# main.net
KiCad netlist of a schematic drawn in EAGLE
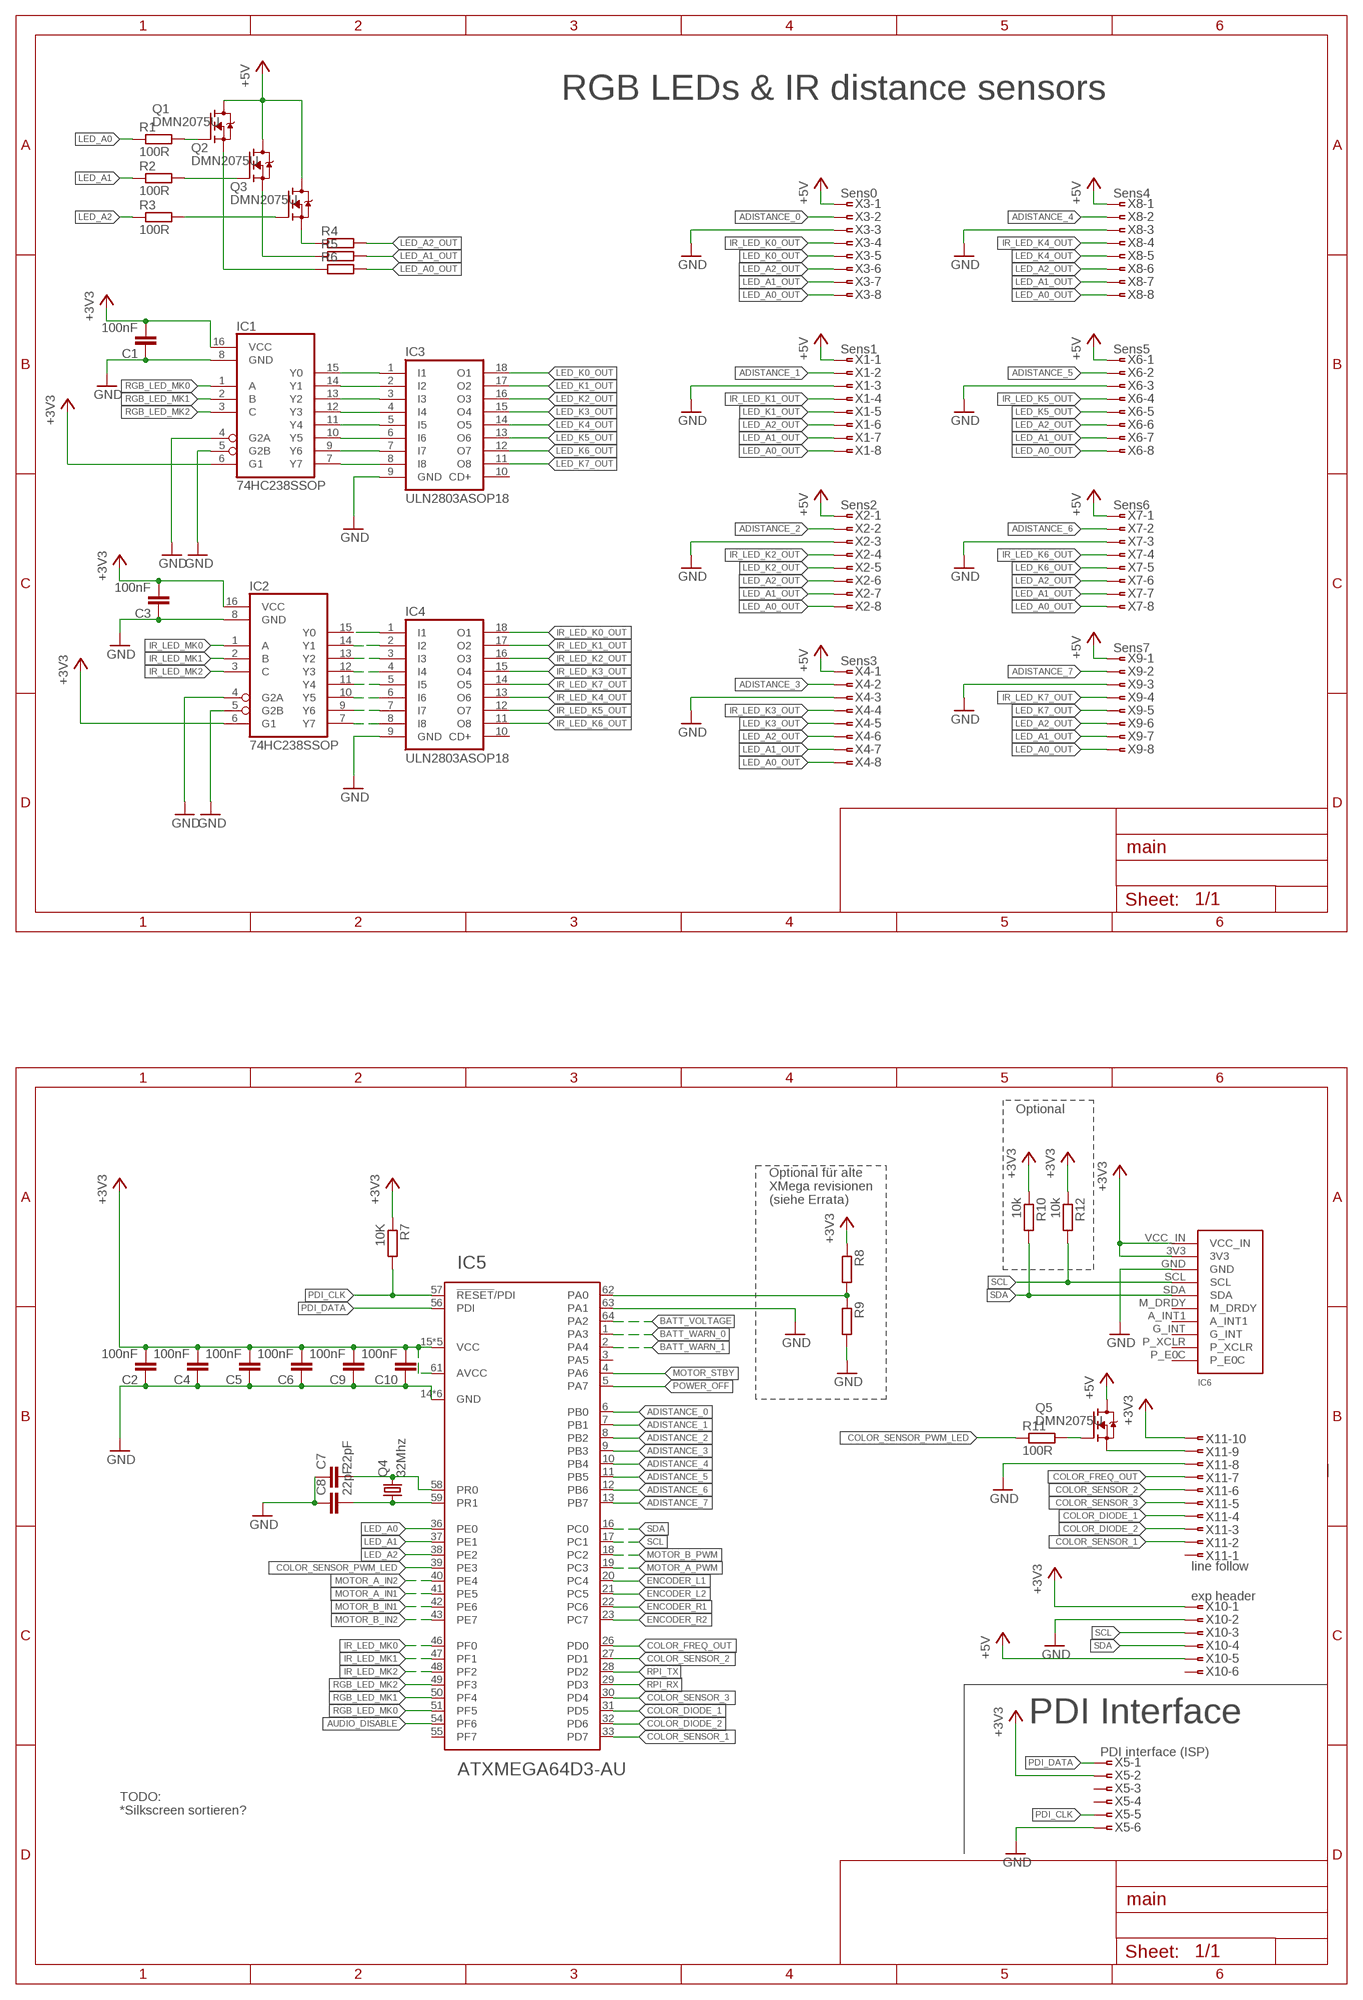
[diagram p0: schematic, sheet 1, part 1 of 2]
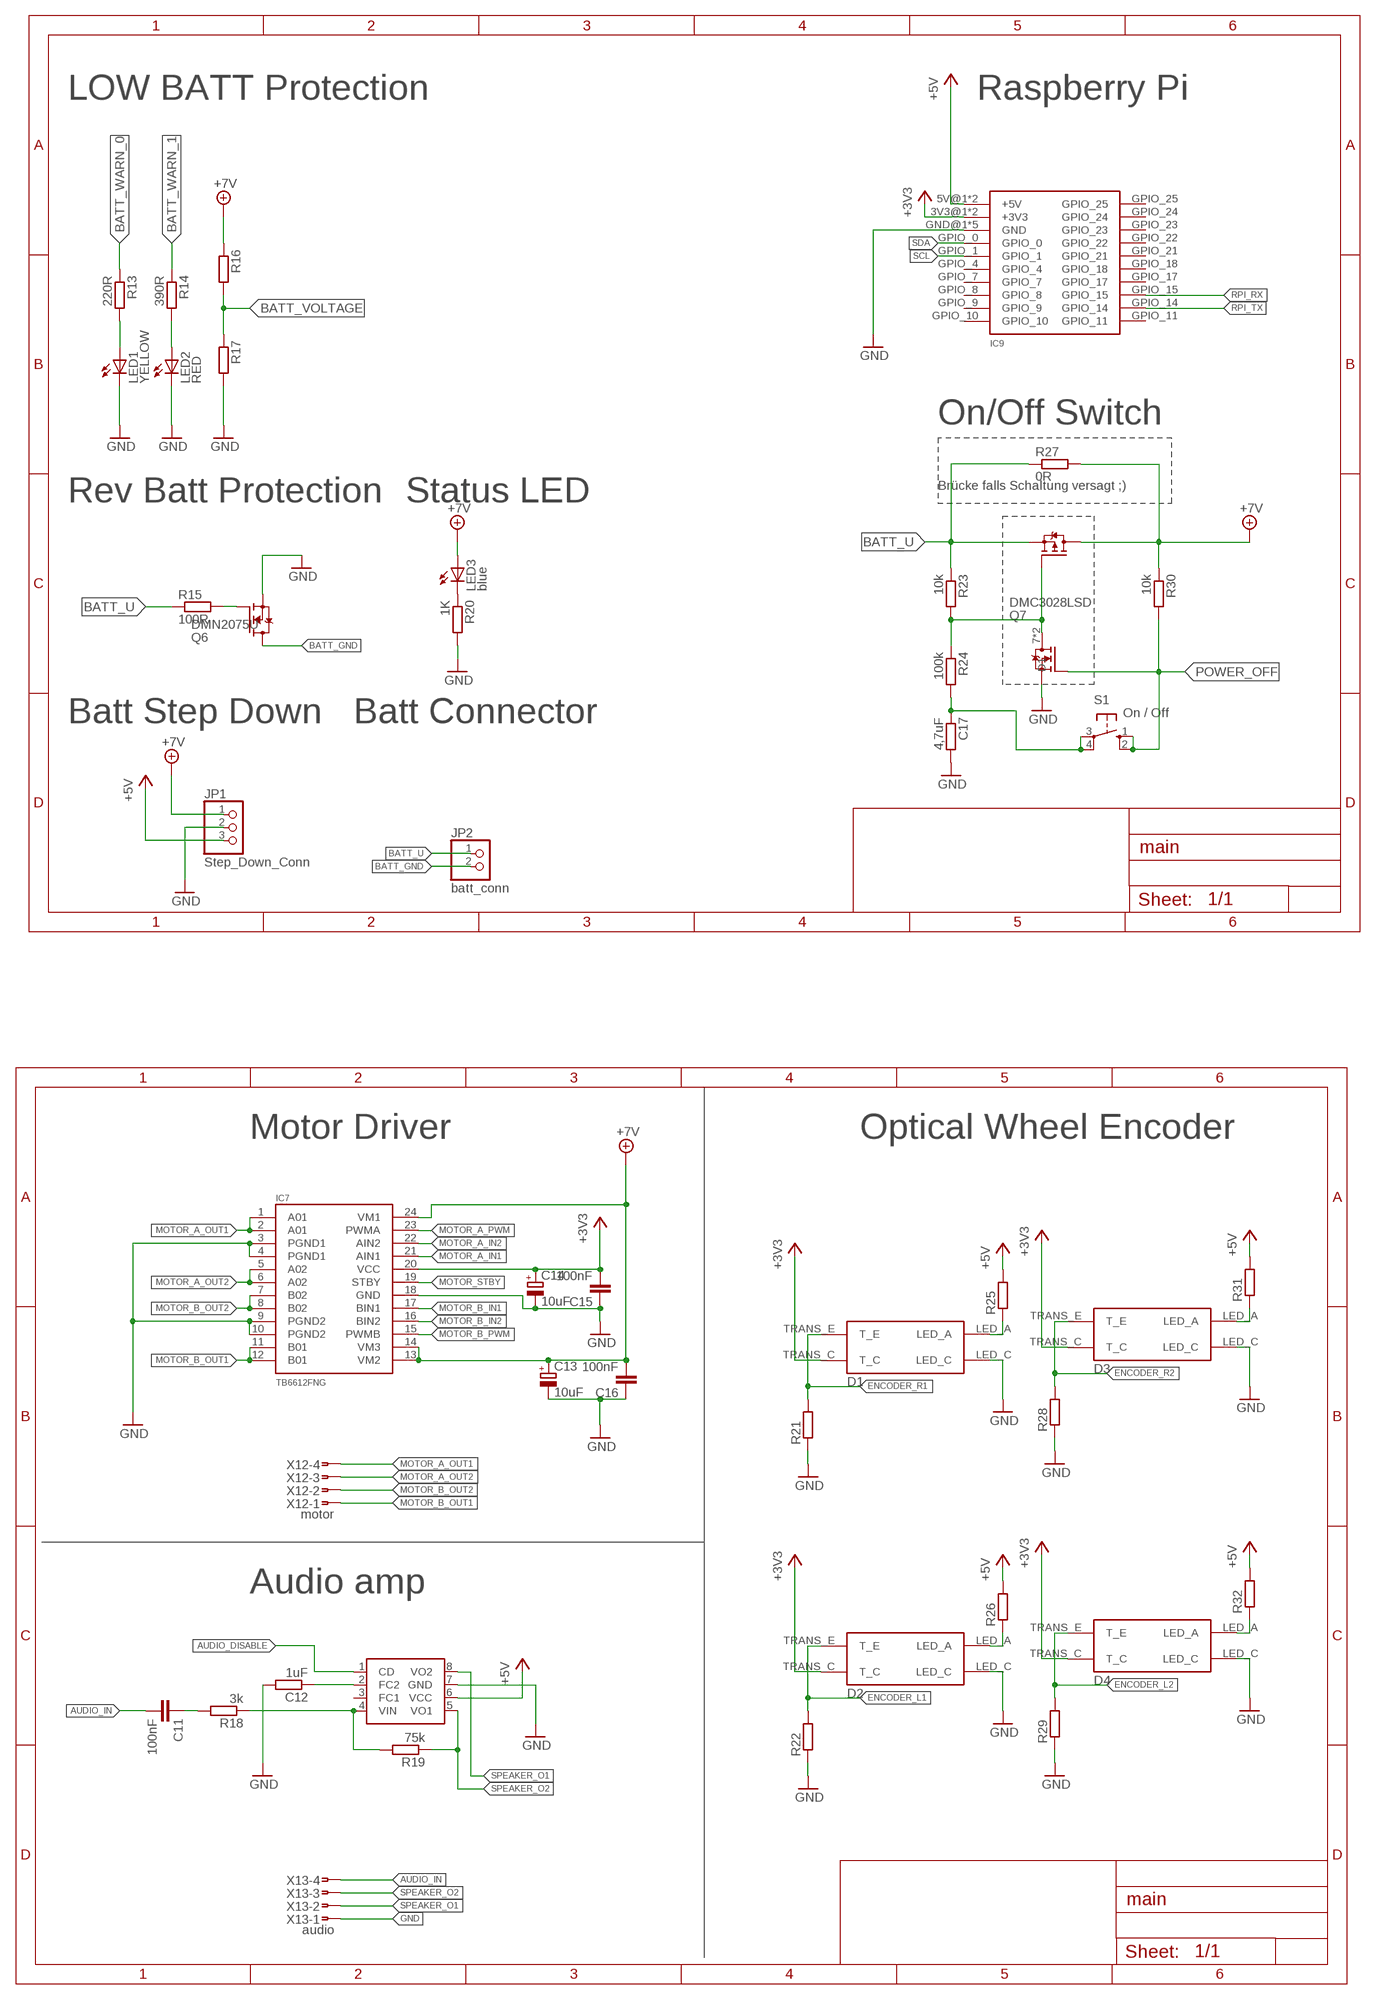
[diagram p1: schematic, sheet 1, part 2 of 2]

(export (version "E")
  (design (tool "Eeschema 10.0.6"))
  (components
    (comp (ref "C1")
      (value "100nF")
      (footprint "eagle-import:C0603")
      (libsource (lib "eagle-import") (part "C-EUC0603"))
    )
    (comp (ref "C2")
      (value "100nF")
      (footprint "eagle-import:C0603")
      (libsource (lib "eagle-import") (part "C-EUC0603"))
    )
    (comp (ref "C3")
      (value "100nF")
      (footprint "eagle-import:C0603")
      (libsource (lib "eagle-import") (part "C-EUC0603"))
    )
    (comp (ref "C4")
      (value "100nF")
      (footprint "eagle-import:C0603")
      (libsource (lib "eagle-import") (part "C-EUC0603"))
    )
    (comp (ref "C5")
      (value "100nF")
      (footprint "eagle-import:C0603")
      (libsource (lib "eagle-import") (part "C-EUC0603"))
    )
    (comp (ref "C6")
      (value "100nF")
      (footprint "eagle-import:C0603")
      (libsource (lib "eagle-import") (part "C-EUC0603"))
    )
    (comp (ref "C7")
      (value "22pF")
      (footprint "eagle-import:C0603")
      (libsource (lib "eagle-import") (part "C-EUC0603"))
    )
    (comp (ref "C8")
      (value "22pF")
      (footprint "eagle-import:C0603")
      (libsource (lib "eagle-import") (part "C-EUC0603"))
    )
    (comp (ref "C9")
      (value "100nF")
      (footprint "eagle-import:C0603")
      (libsource (lib "eagle-import") (part "C-EUC0603"))
    )
    (comp (ref "C10")
      (value "100nF")
      (footprint "eagle-import:C0603")
      (libsource (lib "eagle-import") (part "C-EUC0603"))
    )
    (comp (ref "C11")
      (value "100nF")
      (footprint "eagle-import:C0603")
      (libsource (lib "eagle-import") (part "C-EUC0603"))
    )
    (comp (ref "C12")
      (value "1uF")
      (footprint "eagle-import:M0805")
      (libsource (lib "eagle-import") (part "resistor_R-EU_M0805"))
    )
    (comp (ref "C13")
      (value "10uF")
      (footprint "eagle-import:E2-5")
      (libsource (lib "eagle-import") (part "CPOL-EUE2-5"))
    )
    (comp (ref "C14")
      (value "10uF")
      (footprint "eagle-import:E2-5")
      (libsource (lib "eagle-import") (part "CPOL-EUE2-5"))
    )
    (comp (ref "C15")
      (value "100nF")
      (footprint "eagle-import:C0603")
      (libsource (lib "eagle-import") (part "C-EUC0603"))
    )
    (comp (ref "C16")
      (value "100nF")
      (footprint "eagle-import:C0603")
      (libsource (lib "eagle-import") (part "C-EUC0603"))
    )
    (comp (ref "C17")
      (value "4,7uF")
      (footprint "eagle-import:M0805")
      (libsource (lib "eagle-import") (part "resistor_R-EU_M0805"))
    )
    (comp (ref "D1")
      (value "CNY70")
      (footprint "eagle-import:CNY70")
      (libsource (lib "eagle-import") (part "CNY70"))
    )
    (comp (ref "D2")
      (value "CNY70")
      (footprint "eagle-import:CNY70")
      (libsource (lib "eagle-import") (part "CNY70"))
    )
    (comp (ref "D3")
      (value "CNY70")
      (footprint "eagle-import:CNY70")
      (libsource (lib "eagle-import") (part "CNY70"))
    )
    (comp (ref "D4")
      (value "CNY70")
      (footprint "eagle-import:CNY70")
      (libsource (lib "eagle-import") (part "CNY70"))
    )
    (comp (ref "IC1")
      (value "74HC238SSOP")
      (footprint "eagle-import:SSOP16")
      (libsource (lib "eagle-import") (part "74HC238SSOP"))
    )
    (comp (ref "IC2")
      (value "74HC238SSOP")
      (footprint "eagle-import:SSOP16")
      (libsource (lib "eagle-import") (part "74HC238SSOP"))
    )
    (comp (ref "IC3")
      (value "ULN2803ASOP18")
      (footprint "eagle-import:SOP18")
      (libsource (lib "eagle-import") (part "ULN2803ASOP18"))
    )
    (comp (ref "IC4")
      (value "ULN2803ASOP18")
      (footprint "eagle-import:SOP18")
      (libsource (lib "eagle-import") (part "ULN2803ASOP18"))
    )
    (comp (ref "IC5")
      (value "ATXMEGA64D3-AU")
      (footprint "eagle-import:TQFP-64A-64")
      (libsource (lib "eagle-import") (part "ATXMEGA64D3-AU"))
    )
    (comp (ref "IC6")
      (value "GY-81")
      (footprint "eagle-import:GY-81")
      (libsource (lib "eagle-import") (part "GY-81"))
    )
    (comp (ref "IC7")
      (value "TB6612FNG")
      (footprint "eagle-import:SSOP24")
      (libsource (lib "eagle-import") (part "TB6621FNG"))
    )
    (comp (ref "IC8")
      (value "TS34119SMD")
      (footprint "eagle-import:SO08")
      (libsource (lib "eagle-import") (part "TS34119SMD"))
    )
    (comp (ref "IC9")
      (value "RASPBERRY-PI")
      (footprint "eagle-import:RASPERRRY-PI")
      (libsource (lib "eagle-import") (part "RASPBERRY-PI"))
    )
    (comp (ref "JP1")
      (value "Step_Down_Conn")
      (footprint "eagle-import:1X03")
      (libsource (lib "eagle-import") (part "PINHD-1X3"))
    )
    (comp (ref "JP2")
      (value "batt_conn")
      (footprint "eagle-import:1X02")
      (libsource (lib "eagle-import") (part "PINHD-1X2"))
    )
    (comp (ref "LED1")
      (value "YELLOW")
      (footprint "eagle-import:CHIPLED_0603")
      (libsource (lib "eagle-import") (part "LEDCHIPLED_0603"))
    )
    (comp (ref "LED2")
      (value "RED")
      (footprint "eagle-import:CHIPLED_0603")
      (libsource (lib "eagle-import") (part "LEDCHIPLED_0603"))
    )
    (comp (ref "LED3")
      (value "blue")
      (footprint "eagle-import:CHIPLED_0603")
      (libsource (lib "eagle-import") (part "LEDCHIPLED_0603"))
    )
    (comp (ref "Q1")
      (value "DMN2075U")
      (footprint "eagle-import:SOT95P240X112-3N")
      (libsource (lib "eagle-import") (part "DMN2075U"))
    )
    (comp (ref "Q2")
      (value "DMN2075U")
      (footprint "eagle-import:SOT95P240X112-3N")
      (libsource (lib "eagle-import") (part "DMN2075U"))
    )
    (comp (ref "Q3")
      (value "DMN2075U")
      (footprint "eagle-import:SOT95P240X112-3N")
      (libsource (lib "eagle-import") (part "DMN2075U"))
    )
    (comp (ref "Q4")
      (value "32Mhz")
      (footprint "eagle-import:HC18U-V")
      (libsource (lib "eagle-import") (part "CRYSTALHC18U-V"))
    )
    (comp (ref "Q5")
      (value "DMN2075U")
      (footprint "eagle-import:SOT95P240X112-3N")
      (libsource (lib "eagle-import") (part "DMN2075U"))
    )
    (comp (ref "Q6")
      (value "DMN2075U")
      (footprint "eagle-import:SOT95P240X112-3N")
      (libsource (lib "eagle-import") (part "DMN2075U"))
    )
    (comp (ref "Q7")
      (value "DMC3028LSD")
      (footprint "eagle-import:SO08")
      (libsource (lib "eagle-import") (part "DMC3028LSD"))
    )
    (comp (ref "R1")
      (value "100R")
      (footprint "eagle-import:R0603")
      (libsource (lib "eagle-import") (part "R-EU_R0603"))
    )
    (comp (ref "R2")
      (value "100R")
      (footprint "eagle-import:R0603")
      (libsource (lib "eagle-import") (part "R-EU_R0603"))
    )
    (comp (ref "R3")
      (value "100R")
      (footprint "eagle-import:R0603")
      (libsource (lib "eagle-import") (part "R-EU_R0603"))
    )
    (comp (ref "R4")
      (value "R-EU_M0805")
      (footprint "eagle-import:M0805")
      (libsource (lib "eagle-import") (part "resistor_R-EU_M0805"))
    )
    (comp (ref "R5")
      (value "R-EU_M0805")
      (footprint "eagle-import:M0805")
      (libsource (lib "eagle-import") (part "resistor_R-EU_M0805"))
    )
    (comp (ref "R6")
      (value "R-EU_M0805")
      (footprint "eagle-import:M0805")
      (libsource (lib "eagle-import") (part "resistor_R-EU_M0805"))
    )
    (comp (ref "R7")
      (value "10K")
      (footprint "eagle-import:M0805")
      (libsource (lib "eagle-import") (part "resistor_R-EU_M0805"))
    )
    (comp (ref "R8")
      (value "R-EU_M0805")
      (footprint "eagle-import:M0805")
      (libsource (lib "eagle-import") (part "R-EU_M0805"))
    )
    (comp (ref "R9")
      (value "R-EU_M0805")
      (footprint "eagle-import:M0805")
      (libsource (lib "eagle-import") (part "R-EU_M0805"))
    )
    (comp (ref "R10")
      (value "10k")
      (footprint "eagle-import:M0805")
      (libsource (lib "eagle-import") (part "resistor_R-EU_M0805"))
    )
    (comp (ref "R11")
      (value "100R")
      (footprint "eagle-import:R0603")
      (libsource (lib "eagle-import") (part "R-EU_R0603"))
    )
    (comp (ref "R12")
      (value "10k")
      (footprint "eagle-import:M0805")
      (libsource (lib "eagle-import") (part "resistor_R-EU_M0805"))
    )
    (comp (ref "R13")
      (value "220R")
      (footprint "eagle-import:M0805")
      (libsource (lib "eagle-import") (part "resistor_R-EU_M0805"))
    )
    (comp (ref "R14")
      (value "390R")
      (footprint "eagle-import:M0805")
      (libsource (lib "eagle-import") (part "resistor_R-EU_M0805"))
    )
    (comp (ref "R15")
      (value "100R")
      (footprint "eagle-import:R0603")
      (libsource (lib "eagle-import") (part "R-EU_R0603"))
    )
    (comp (ref "R16")
      (value "R-EU_M0805")
      (footprint "eagle-import:M0805")
      (libsource (lib "eagle-import") (part "resistor_R-EU_M0805"))
    )
    (comp (ref "R17")
      (value "R-EU_M0805")
      (footprint "eagle-import:M0805")
      (libsource (lib "eagle-import") (part "resistor_R-EU_M0805"))
    )
    (comp (ref "R18")
      (value "3k")
      (footprint "eagle-import:M0805")
      (libsource (lib "eagle-import") (part "resistor_R-EU_M0805"))
    )
    (comp (ref "R19")
      (value "75k")
      (footprint "eagle-import:M0805")
      (libsource (lib "eagle-import") (part "resistor_R-EU_M0805"))
    )
    (comp (ref "R20")
      (value "1K")
      (footprint "eagle-import:M0805")
      (libsource (lib "eagle-import") (part "resistor_R-EU_M0805"))
    )
    (comp (ref "R21")
      (value "R-EU_M0805")
      (footprint "eagle-import:M0805")
      (libsource (lib "eagle-import") (part "resistor_R-EU_M0805"))
    )
    (comp (ref "R22")
      (value "R-EU_M0805")
      (footprint "eagle-import:M0805")
      (libsource (lib "eagle-import") (part "resistor_R-EU_M0805"))
    )
    (comp (ref "R23")
      (value "10k")
      (footprint "eagle-import:M0805")
      (libsource (lib "eagle-import") (part "resistor_R-EU_M0805"))
    )
    (comp (ref "R24")
      (value "100k")
      (footprint "eagle-import:M0805")
      (libsource (lib "eagle-import") (part "resistor_R-EU_M0805"))
    )
    (comp (ref "R25")
      (value "R-EU_M0805")
      (footprint "eagle-import:M0805")
      (libsource (lib "eagle-import") (part "resistor_R-EU_M0805"))
    )
    (comp (ref "R26")
      (value "R-EU_M0805")
      (footprint "eagle-import:M0805")
      (libsource (lib "eagle-import") (part "resistor_R-EU_M0805"))
    )
    (comp (ref "R27")
      (value "0R")
      (footprint "eagle-import:M0805")
      (libsource (lib "eagle-import") (part "resistor_R-EU_M0805"))
    )
    (comp (ref "R28")
      (value "R-EU_M0805")
      (footprint "eagle-import:M0805")
      (libsource (lib "eagle-import") (part "resistor_R-EU_M0805"))
    )
    (comp (ref "R29")
      (value "R-EU_M0805")
      (footprint "eagle-import:M0805")
      (libsource (lib "eagle-import") (part "resistor_R-EU_M0805"))
    )
    (comp (ref "R30")
      (value "10k")
      (footprint "eagle-import:M0805")
      (libsource (lib "eagle-import") (part "resistor_R-EU_M0805"))
    )
    (comp (ref "R31")
      (value "R-EU_M0805")
      (footprint "eagle-import:M0805")
      (libsource (lib "eagle-import") (part "resistor_R-EU_M0805"))
    )
    (comp (ref "R32")
      (value "R-EU_M0805")
      (footprint "eagle-import:M0805")
      (libsource (lib "eagle-import") (part "resistor_R-EU_M0805"))
    )
    (comp (ref "S1")
      (value "On / Off")
      (footprint "eagle-import:B3F-10XX")
      (fields (field (name "MPN") "B3F-1000"))
      (libsource (lib "eagle-import") (part "10-XX"))
    )
    (comp (ref "X1")
      (value "Sens1")
      (footprint "eagle-import:FSIDE-8")
      (libsource (lib "eagle-import") (part "FSIDE-8"))
    )
    (comp (ref "X2")
      (value "Sens2")
      (footprint "eagle-import:FSIDE-8")
      (libsource (lib "eagle-import") (part "FSIDE-8"))
    )
    (comp (ref "X3")
      (value "Sens0")
      (footprint "eagle-import:FTOP-8")
      (libsource (lib "eagle-import") (part "FTOP-8"))
    )
    (comp (ref "X4")
      (value "Sens3")
      (footprint "eagle-import:FTOP-8")
      (libsource (lib "eagle-import") (part "FTOP-8"))
    )
    (comp (ref "X5")
      (value "PDI interface (ISP)")
      (footprint "eagle-import:FTOP-6")
      (libsource (lib "eagle-import") (part "FTOP-6"))
    )
    (comp (ref "X6")
      (value "Sens5")
      (footprint "eagle-import:FSIDE-8")
      (libsource (lib "eagle-import") (part "FSIDE-8"))
    )
    (comp (ref "X7")
      (value "Sens6")
      (footprint "eagle-import:FSIDE-8")
      (libsource (lib "eagle-import") (part "FSIDE-8"))
    )
    (comp (ref "X8")
      (value "Sens4")
      (footprint "eagle-import:FTOP-8")
      (libsource (lib "eagle-import") (part "FTOP-8"))
    )
    (comp (ref "X9")
      (value "Sens7")
      (footprint "eagle-import:FTOP-8")
      (libsource (lib "eagle-import") (part "FTOP-8"))
    )
    (comp (ref "X10")
      (value "exp header")
      (footprint "eagle-import:FTOP-6")
      (libsource (lib "eagle-import") (part "FTOP-6"))
    )
    (comp (ref "X11")
      (value "line follow")
      (footprint "eagle-import:FTOP-10")
      (libsource (lib "eagle-import") (part "FTOP-10"))
    )
    (comp (ref "X12")
      (value "motor")
      (footprint "eagle-import:FTOP-4")
      (libsource (lib "eagle-import") (part "FTOP-4"))
    )
    (comp (ref "X13")
      (value "audio")
      (footprint "eagle-import:FTOP-4")
      (libsource (lib "eagle-import") (part "FTOP-4"))
    )
  )
  (nets
    (net (code "1") (name "+3V3") (class "Default")
      (node (ref "C1") (pin "2") (pinfunction "2_2") (pintype "passive"))
      (node (ref "C10") (pin "2") (pinfunction "2_2") (pintype "passive"))
      (node (ref "C14") (pin "+") (pinfunction "+_+") (pintype "passive"))
      (node (ref "C15") (pin "2") (pinfunction "2_2") (pintype "passive"))
      (node (ref "C2") (pin "2") (pinfunction "2_2") (pintype "passive"))
      (node (ref "C3") (pin "2") (pinfunction "2_2") (pintype "passive"))
      (node (ref "C4") (pin "2") (pinfunction "2_2") (pintype "passive"))
      (node (ref "C5") (pin "2") (pinfunction "2_2") (pintype "passive"))
      (node (ref "C6") (pin "2") (pinfunction "2_2") (pintype "passive"))
      (node (ref "C9") (pin "2") (pinfunction "2_2") (pintype "passive"))
      (node (ref "D1") (pin "TRANS_C") (pinfunction "T_C_TRANS_C") (pintype "bidirectional"))
      (node (ref "D2") (pin "TRANS_C") (pinfunction "T_C_TRANS_C") (pintype "bidirectional"))
      (node (ref "D3") (pin "TRANS_C") (pinfunction "T_C_TRANS_C") (pintype "bidirectional"))
      (node (ref "D4") (pin "TRANS_C") (pinfunction "T_C_TRANS_C") (pintype "bidirectional"))
      (node (ref "IC1") (pin "16") (pinfunction "VCC_16") (pintype "power_in"))
      (node (ref "IC1") (pin "6") (pinfunction "G1_6") (pintype "input"))
      (node (ref "IC2") (pin "16") (pinfunction "VCC_16") (pintype "power_in"))
      (node (ref "IC2") (pin "6") (pinfunction "G1_6") (pintype "input"))
      (node (ref "IC5") (pin "15") (pinfunction "VCC_15") (pintype "power_in"))
      (node (ref "IC5") (pin "25") (pinfunction "VCC_25") (pintype "power_in"))
      (node (ref "IC5") (pin "35") (pinfunction "VCC_35") (pintype "power_in"))
      (node (ref "IC5") (pin "45") (pinfunction "VCC_45") (pintype "power_in"))
      (node (ref "IC5") (pin "53") (pinfunction "VCC_53") (pintype "power_in"))
      (node (ref "IC5") (pin "61") (pinfunction "AVCC_61") (pintype "power_in"))
      (node (ref "IC6") (pin "3V3") (pinfunction "3V3_3V3") (pintype "bidirectional"))
      (node (ref "IC6") (pin "VCC_IN") (pinfunction "VCC_IN_VCC_IN") (pintype "bidirectional"))
      (node (ref "IC7") (pin "20") (pinfunction "VCC_20") (pintype "bidirectional"))
      (node (ref "IC9") (pin "3V3@1") (pinfunction "+3V3_3V3@1") (pintype "power_in"))
      (node (ref "IC9") (pin "3V3@2") (pinfunction "+3V3_3V3@2") (pintype "power_in"))
      (node (ref "R10") (pin "1") (pinfunction "1_1") (pintype "passive"))
      (node (ref "R12") (pin "1") (pinfunction "1_1") (pintype "passive"))
      (node (ref "R7") (pin "1") (pinfunction "1_1") (pintype "passive"))
      (node (ref "R8") (pin "1") (pinfunction "1_1") (pintype "passive"))
      (node (ref "X10") (pin "1") (pinfunction "1_1") (pintype "passive"))
      (node (ref "X11") (pin "10") (pinfunction "1_10") (pintype "passive"))
      (node (ref "X5") (pin "2") (pinfunction "1_2") (pintype "passive"))
    )
    (net (code "2") (name "+5V") (class "Default")
      (node (ref "IC8") (pin "6") (pinfunction "VCC_6") (pintype "bidirectional"))
      (node (ref "IC9") (pin "5V@1") (pinfunction "+5V_5V@1") (pintype "power_in"))
      (node (ref "IC9") (pin "5V@2") (pinfunction "+5V_5V@2") (pintype "power_in"))
      (node (ref "JP1") (pin "3") (pinfunction "3_3") (pintype "passive"))
      (node (ref "Q1") (pin "D") (pinfunction "D_D") (pintype "passive"))
      (node (ref "Q2") (pin "D") (pinfunction "D_D") (pintype "passive"))
      (node (ref "Q3") (pin "D") (pinfunction "D_D") (pintype "passive"))
      (node (ref "Q5") (pin "D") (pinfunction "D_D") (pintype "passive"))
      (node (ref "R25") (pin "2") (pinfunction "2_2") (pintype "passive"))
      (node (ref "R26") (pin "2") (pinfunction "2_2") (pintype "passive"))
      (node (ref "R31") (pin "2") (pinfunction "2_2") (pintype "passive"))
      (node (ref "R32") (pin "2") (pinfunction "2_2") (pintype "passive"))
      (node (ref "X1") (pin "1") (pinfunction "1_1") (pintype "passive"))
      (node (ref "X10") (pin "5") (pinfunction "1_5") (pintype "passive"))
      (node (ref "X2") (pin "1") (pinfunction "1_1") (pintype "passive"))
      (node (ref "X3") (pin "1") (pinfunction "1_1") (pintype "passive"))
      (node (ref "X4") (pin "1") (pinfunction "1_1") (pintype "passive"))
      (node (ref "X6") (pin "1") (pinfunction "1_1") (pintype "passive"))
      (node (ref "X7") (pin "1") (pinfunction "1_1") (pintype "passive"))
      (node (ref "X8") (pin "1") (pinfunction "1_1") (pintype "passive"))
      (node (ref "X9") (pin "1") (pinfunction "1_1") (pintype "passive"))
    )
    (net (code "3") (name "+7V") (class "Default")
      (node (ref "C13") (pin "+") (pinfunction "+_+") (pintype "passive"))
      (node (ref "C16") (pin "2") (pinfunction "2_2") (pintype "passive"))
      (node (ref "IC7") (pin "13") (pinfunction "VM2_13") (pintype "bidirectional"))
      (node (ref "IC7") (pin "14") (pinfunction "VM3_14") (pintype "bidirectional"))
      (node (ref "IC7") (pin "24") (pinfunction "VM1_24") (pintype "bidirectional"))
      (node (ref "JP1") (pin "1") (pinfunction "1_1") (pintype "passive"))
      (node (ref "LED3") (pin "A") (pinfunction "A_A") (pintype "passive"))
      (node (ref "Q7") (pin "5") (pinfunction "D2_5") (pintype "passive"))
      (node (ref "Q7") (pin "6") (pinfunction "D2_6") (pintype "passive"))
      (node (ref "R16") (pin "1") (pinfunction "1_1") (pintype "passive"))
      (node (ref "R27") (pin "2") (pinfunction "2_2") (pintype "passive"))
      (node (ref "R30") (pin "1") (pinfunction "1_1") (pintype "passive"))
    )
    (net (code "4") (name "ADISTANCE_0") (class "Default")
      (node (ref "IC5") (pin "6") (pinfunction "PB0_6") (pintype "bidirectional"))
      (node (ref "X3") (pin "2") (pinfunction "1_2") (pintype "passive"))
    )
    (net (code "5") (name "ADISTANCE_1") (class "Default")
      (node (ref "IC5") (pin "7") (pinfunction "PB1_7") (pintype "bidirectional"))
      (node (ref "X1") (pin "2") (pinfunction "1_2") (pintype "passive"))
    )
    (net (code "6") (name "ADISTANCE_2") (class "Default")
      (node (ref "IC5") (pin "8") (pinfunction "PB2_8") (pintype "bidirectional"))
      (node (ref "X2") (pin "2") (pinfunction "1_2") (pintype "passive"))
    )
    (net (code "7") (name "ADISTANCE_3") (class "Default")
      (node (ref "IC5") (pin "9") (pinfunction "PB3_9") (pintype "bidirectional"))
      (node (ref "X4") (pin "2") (pinfunction "1_2") (pintype "passive"))
    )
    (net (code "8") (name "ADISTANCE_4") (class "Default")
      (node (ref "IC5") (pin "10") (pinfunction "PB4_10") (pintype "bidirectional"))
      (node (ref "X8") (pin "2") (pinfunction "1_2") (pintype "passive"))
    )
    (net (code "9") (name "ADISTANCE_5") (class "Default")
      (node (ref "IC5") (pin "11") (pinfunction "PB5_11") (pintype "bidirectional"))
      (node (ref "X6") (pin "2") (pinfunction "1_2") (pintype "passive"))
    )
    (net (code "10") (name "ADISTANCE_6") (class "Default")
      (node (ref "IC5") (pin "12") (pinfunction "PB6_12") (pintype "bidirectional"))
      (node (ref "X7") (pin "2") (pinfunction "1_2") (pintype "passive"))
    )
    (net (code "11") (name "ADISTANCE_7") (class "Default")
      (node (ref "IC5") (pin "13") (pinfunction "PB7_13") (pintype "bidirectional"))
      (node (ref "X9") (pin "2") (pinfunction "1_2") (pintype "passive"))
    )
    (net (code "12") (name "AUDIO_DISABLE") (class "Default")
      (node (ref "IC5") (pin "54") (pinfunction "PF6_54") (pintype "bidirectional"))
      (node (ref "IC8") (pin "1") (pinfunction "CD_1") (pintype "bidirectional"))
    )
    (net (code "13") (name "AUDIO_IN") (class "Default")
      (node (ref "C11") (pin "2") (pinfunction "2_2") (pintype "passive"))
      (node (ref "X13") (pin "4") (pinfunction "1_4") (pintype "passive"))
    )
    (net (code "14") (name "BATT_GND") (class "Default")
      (node (ref "JP2") (pin "2") (pinfunction "2_2") (pintype "passive"))
      (node (ref "Q6") (pin "D") (pinfunction "D_D") (pintype "passive"))
    )
    (net (code "15") (name "BATT_U") (class "Default")
      (node (ref "JP2") (pin "1") (pinfunction "1_1") (pintype "passive"))
      (node (ref "Q7") (pin "3") (pinfunction "S2_3") (pintype "passive"))
      (node (ref "R15") (pin "1") (pinfunction "1_1") (pintype "passive"))
      (node (ref "R23") (pin "1") (pinfunction "1_1") (pintype "passive"))
      (node (ref "R27") (pin "1") (pinfunction "1_1") (pintype "passive"))
    )
    (net (code "16") (name "BATT_VOLTAGE") (class "Default")
      (node (ref "IC5") (pin "64") (pinfunction "PA2_64") (pintype "bidirectional"))
      (node (ref "R16") (pin "2") (pinfunction "2_2") (pintype "passive"))
      (node (ref "R17") (pin "1") (pinfunction "1_1") (pintype "passive"))
    )
    (net (code "17") (name "BATT_WARN_0") (class "Default")
      (node (ref "IC5") (pin "1") (pinfunction "PA3_1") (pintype "bidirectional"))
      (node (ref "R13") (pin "1") (pinfunction "1_1") (pintype "passive"))
    )
    (net (code "18") (name "BATT_WARN_1") (class "Default")
      (node (ref "IC5") (pin "2") (pinfunction "PA4_2") (pintype "bidirectional"))
      (node (ref "R14") (pin "1") (pinfunction "1_1") (pintype "passive"))
    )
    (net (code "19") (name "COLOR_DIODE_1") (class "Default")
      (node (ref "IC5") (pin "31") (pinfunction "PD5_31") (pintype "bidirectional"))
      (node (ref "X11") (pin "4") (pinfunction "1_4") (pintype "passive"))
    )
    (net (code "20") (name "COLOR_DIODE_2") (class "Default")
      (node (ref "IC5") (pin "32") (pinfunction "PD6_32") (pintype "bidirectional"))
      (node (ref "X11") (pin "3") (pinfunction "1_3") (pintype "passive"))
    )
    (net (code "21") (name "COLOR_FREQ_OUT") (class "Default")
      (node (ref "IC5") (pin "26") (pinfunction "PD0_26") (pintype "bidirectional"))
      (node (ref "X11") (pin "7") (pinfunction "1_7") (pintype "passive"))
    )
    (net (code "22") (name "COLOR_SENSOR_1") (class "Default")
      (node (ref "IC5") (pin "33") (pinfunction "PD7_33") (pintype "bidirectional"))
      (node (ref "X11") (pin "2") (pinfunction "1_2") (pintype "passive"))
    )
    (net (code "23") (name "COLOR_SENSOR_2") (class "Default")
      (node (ref "IC5") (pin "27") (pinfunction "PD1_27") (pintype "bidirectional"))
      (node (ref "X11") (pin "6") (pinfunction "1_6") (pintype "passive"))
    )
    (net (code "24") (name "COLOR_SENSOR_3") (class "Default")
      (node (ref "IC5") (pin "30") (pinfunction "PD4_30") (pintype "bidirectional"))
      (node (ref "X11") (pin "5") (pinfunction "1_5") (pintype "passive"))
    )
    (net (code "25") (name "COLOR_SENSOR_PWM_LED") (class "Default")
      (node (ref "IC5") (pin "39") (pinfunction "PE3_39") (pintype "bidirectional"))
      (node (ref "R11") (pin "1") (pinfunction "1_1") (pintype "passive"))
    )
    (net (code "26") (name "ENCODER_L1") (class "Default")
      (node (ref "D2") (pin "TRANS_E") (pinfunction "T_E_TRANS_E") (pintype "bidirectional"))
      (node (ref "IC5") (pin "20") (pinfunction "PC4_20") (pintype "bidirectional"))
      (node (ref "R22") (pin "2") (pinfunction "2_2") (pintype "passive"))
    )
    (net (code "27") (name "ENCODER_L2") (class "Default")
      (node (ref "D4") (pin "TRANS_E") (pinfunction "T_E_TRANS_E") (pintype "bidirectional"))
      (node (ref "IC5") (pin "21") (pinfunction "PC5_21") (pintype "bidirectional"))
      (node (ref "R29") (pin "2") (pinfunction "2_2") (pintype "passive"))
    )
    (net (code "28") (name "ENCODER_R1") (class "Default")
      (node (ref "D1") (pin "TRANS_E") (pinfunction "T_E_TRANS_E") (pintype "bidirectional"))
      (node (ref "IC5") (pin "22") (pinfunction "PC6_22") (pintype "bidirectional"))
      (node (ref "R21") (pin "2") (pinfunction "2_2") (pintype "passive"))
    )
    (net (code "29") (name "ENCODER_R2") (class "Default")
      (node (ref "D3") (pin "TRANS_E") (pinfunction "T_E_TRANS_E") (pintype "bidirectional"))
      (node (ref "IC5") (pin "23") (pinfunction "PC7_23") (pintype "bidirectional"))
      (node (ref "R28") (pin "2") (pinfunction "2_2") (pintype "passive"))
    )
    (net (code "30") (name "GND") (class "Default")
      (node (ref "C1") (pin "1") (pinfunction "1_1") (pintype "passive"))
      (node (ref "C10") (pin "1") (pinfunction "1_1") (pintype "passive"))
      (node (ref "C12") (pin "2") (pinfunction "2_2") (pintype "passive"))
      (node (ref "C13") (pin "-") (pinfunction "-_-") (pintype "passive"))
      (node (ref "C14") (pin "-") (pinfunction "-_-") (pintype "passive"))
      (node (ref "C15") (pin "1") (pinfunction "1_1") (pintype "passive"))
      (node (ref "C16") (pin "1") (pinfunction "1_1") (pintype "passive"))
      (node (ref "C17") (pin "2") (pinfunction "2_2") (pintype "passive"))
      (node (ref "C2") (pin "1") (pinfunction "1_1") (pintype "passive"))
      (node (ref "C3") (pin "1") (pinfunction "1_1") (pintype "passive"))
      (node (ref "C4") (pin "1") (pinfunction "1_1") (pintype "passive"))
      (node (ref "C5") (pin "1") (pinfunction "1_1") (pintype "passive"))
      (node (ref "C6") (pin "1") (pinfunction "1_1") (pintype "passive"))
      (node (ref "C7") (pin "1") (pinfunction "1_1") (pintype "passive"))
      (node (ref "C8") (pin "1") (pinfunction "1_1") (pintype "passive"))
      (node (ref "C9") (pin "1") (pinfunction "1_1") (pintype "passive"))
      (node (ref "D1") (pin "LED_C") (pinfunction "LED_C_LED_C") (pintype "bidirectional"))
      (node (ref "D2") (pin "LED_C") (pinfunction "LED_C_LED_C") (pintype "bidirectional"))
      (node (ref "D3") (pin "LED_C") (pinfunction "LED_C_LED_C") (pintype "bidirectional"))
      (node (ref "D4") (pin "LED_C") (pinfunction "LED_C_LED_C") (pintype "bidirectional"))
      (node (ref "IC1") (pin "4") (pinfunction "G2A_4") (pintype "input"))
      (node (ref "IC1") (pin "5") (pinfunction "G2B_5") (pintype "input"))
      (node (ref "IC1") (pin "8") (pinfunction "GND_8") (pintype "power_in"))
      (node (ref "IC2") (pin "4") (pinfunction "G2A_4") (pintype "input"))
      (node (ref "IC2") (pin "5") (pinfunction "G2B_5") (pintype "input"))
      (node (ref "IC2") (pin "8") (pinfunction "GND_8") (pintype "power_in"))
      (node (ref "IC3") (pin "9") (pinfunction "GND_9") (pintype "power_in"))
      (node (ref "IC4") (pin "9") (pinfunction "GND_9") (pintype "power_in"))
      (node (ref "IC5") (pin "14") (pinfunction "GND_14") (pintype "power_in"))
      (node (ref "IC5") (pin "24") (pinfunction "GND_24") (pintype "power_in"))
      (node (ref "IC5") (pin "34") (pinfunction "GND_34") (pintype "power_in"))
      (node (ref "IC5") (pin "44") (pinfunction "GND_44") (pintype "power_in"))
      (node (ref "IC5") (pin "52") (pinfunction "GND_52") (pintype "power_in"))
      (node (ref "IC5") (pin "60") (pinfunction "GND_60") (pintype "power_in"))
      (node (ref "IC5") (pin "63") (pinfunction "PA1_63") (pintype "bidirectional"))
      (node (ref "IC6") (pin "GND") (pinfunction "GND_GND") (pintype "bidirectional"))
      (node (ref "IC7") (pin "10") (pinfunction "PGND2_10") (pintype "bidirectional"))
      (node (ref "IC7") (pin "18") (pinfunction "GND_18") (pintype "bidirectional"))
      (node (ref "IC7") (pin "3") (pinfunction "PGND1_3") (pintype "bidirectional"))
      (node (ref "IC7") (pin "4") (pinfunction "PGND1_4") (pintype "bidirectional"))
      (node (ref "IC7") (pin "9") (pinfunction "PGND2_9") (pintype "bidirectional"))
      (node (ref "IC8") (pin "7") (pinfunction "GND_7") (pintype "bidirectional"))
      (node (ref "IC9") (pin "GND@1") (pinfunction "GND_GND@1") (pintype "power_in"))
      (node (ref "IC9") (pin "GND@2") (pinfunction "GND_GND@2") (pintype "power_in"))
      (node (ref "IC9") (pin "GND@3") (pinfunction "GND_GND@3") (pintype "power_in"))
      (node (ref "IC9") (pin "GND@4") (pinfunction "GND_GND@4") (pintype "power_in"))
      (node (ref "IC9") (pin "GND@5") (pinfunction "GND_GND@5") (pintype "power_in"))
      (node (ref "JP1") (pin "2") (pinfunction "2_2") (pintype "passive"))
      (node (ref "LED1") (pin "C") (pinfunction "C_C") (pintype "passive"))
      (node (ref "LED2") (pin "C") (pinfunction "C_C") (pintype "passive"))
      (node (ref "Q6") (pin "S") (pinfunction "S_S") (pintype "passive"))
      (node (ref "Q7") (pin "1") (pinfunction "S1_1") (pintype "passive"))
      (node (ref "R17") (pin "2") (pinfunction "2_2") (pintype "passive"))
      (node (ref "R20") (pin "2") (pinfunction "2_2") (pintype "passive"))
      (node (ref "R21") (pin "1") (pinfunction "1_1") (pintype "passive"))
      (node (ref "R22") (pin "1") (pinfunction "1_1") (pintype "passive"))
      (node (ref "R28") (pin "1") (pinfunction "1_1") (pintype "passive"))
      (node (ref "R29") (pin "1") (pinfunction "1_1") (pintype "passive"))
      (node (ref "R9") (pin "2") (pinfunction "2_2") (pintype "passive"))
      (node (ref "X1") (pin "3") (pinfunction "1_3") (pintype "passive"))
      (node (ref "X10") (pin "2") (pinfunction "1_2") (pintype "passive"))
      (node (ref "X11") (pin "8") (pinfunction "1_8") (pintype "passive"))
      (node (ref "X13") (pin "1") (pinfunction "1_1") (pintype "passive"))
      (node (ref "X2") (pin "3") (pinfunction "1_3") (pintype "passive"))
      (node (ref "X3") (pin "3") (pinfunction "1_3") (pintype "passive"))
      (node (ref "X4") (pin "3") (pinfunction "1_3") (pintype "passive"))
      (node (ref "X5") (pin "6") (pinfunction "1_6") (pintype "passive"))
      (node (ref "X6") (pin "3") (pinfunction "1_3") (pintype "passive"))
      (node (ref "X7") (pin "3") (pinfunction "1_3") (pintype "passive"))
      (node (ref "X8") (pin "3") (pinfunction "1_3") (pintype "passive"))
      (node (ref "X9") (pin "3") (pinfunction "1_3") (pintype "passive"))
    )
    (net (code "31") (name "IR_LED_K0_OUT") (class "Default")
      (node (ref "IC4") (pin "18") (pinfunction "O1_18") (pintype "open_collector"))
      (node (ref "X3") (pin "4") (pinfunction "1_4") (pintype "passive"))
    )
    (net (code "32") (name "IR_LED_K1_OUT") (class "Default")
      (node (ref "IC4") (pin "17") (pinfunction "O2_17") (pintype "open_collector"))
      (node (ref "X1") (pin "4") (pinfunction "1_4") (pintype "passive"))
    )
    (net (code "33") (name "IR_LED_K2_OUT") (class "Default")
      (node (ref "IC4") (pin "16") (pinfunction "O3_16") (pintype "open_collector"))
      (node (ref "X2") (pin "4") (pinfunction "1_4") (pintype "passive"))
    )
    (net (code "34") (name "IR_LED_K3_OUT") (class "Default")
      (node (ref "IC4") (pin "15") (pinfunction "O4_15") (pintype "open_collector"))
      (node (ref "X4") (pin "4") (pinfunction "1_4") (pintype "passive"))
    )
    (net (code "35") (name "IR_LED_K4_OUT") (class "Default")
      (node (ref "IC4") (pin "13") (pinfunction "O6_13") (pintype "open_collector"))
      (node (ref "X8") (pin "4") (pinfunction "1_4") (pintype "passive"))
    )
    (net (code "36") (name "IR_LED_K5_OUT") (class "Default")
      (node (ref "IC4") (pin "12") (pinfunction "O7_12") (pintype "open_collector"))
      (node (ref "X6") (pin "4") (pinfunction "1_4") (pintype "passive"))
    )
    (net (code "37") (name "IR_LED_K6_OUT") (class "Default")
      (node (ref "IC4") (pin "11") (pinfunction "O8_11") (pintype "open_collector"))
      (node (ref "X7") (pin "4") (pinfunction "1_4") (pintype "passive"))
    )
    (net (code "38") (name "IR_LED_K7_OUT") (class "Default")
      (node (ref "IC4") (pin "14") (pinfunction "O5_14") (pintype "open_collector"))
      (node (ref "X9") (pin "4") (pinfunction "1_4") (pintype "passive"))
    )
    (net (code "39") (name "IR_LED_MK0") (class "Default")
      (node (ref "IC2") (pin "1") (pinfunction "A_1") (pintype "input"))
      (node (ref "IC5") (pin "46") (pinfunction "PF0_46") (pintype "bidirectional"))
    )
    (net (code "40") (name "IR_LED_MK1") (class "Default")
      (node (ref "IC2") (pin "2") (pinfunction "B_2") (pintype "input"))
      (node (ref "IC5") (pin "47") (pinfunction "PF1_47") (pintype "bidirectional"))
    )
    (net (code "41") (name "IR_LED_MK2") (class "Default")
      (node (ref "IC2") (pin "3") (pinfunction "C_3") (pintype "input"))
      (node (ref "IC5") (pin "48") (pinfunction "PF2_48") (pintype "bidirectional"))
    )
    (net (code "42") (name "LED_A0") (class "Default")
      (node (ref "IC5") (pin "36") (pinfunction "PE0_36") (pintype "bidirectional"))
      (node (ref "R1") (pin "1") (pinfunction "1_1") (pintype "passive"))
    )
    (net (code "43") (name "LED_A0_OUT") (class "Default")
      (node (ref "R6") (pin "2") (pinfunction "2_2") (pintype "passive"))
      (node (ref "X1") (pin "8") (pinfunction "1_8") (pintype "passive"))
      (node (ref "X2") (pin "8") (pinfunction "1_8") (pintype "passive"))
      (node (ref "X3") (pin "8") (pinfunction "1_8") (pintype "passive"))
      (node (ref "X4") (pin "8") (pinfunction "1_8") (pintype "passive"))
      (node (ref "X6") (pin "8") (pinfunction "1_8") (pintype "passive"))
      (node (ref "X7") (pin "8") (pinfunction "1_8") (pintype "passive"))
      (node (ref "X8") (pin "8") (pinfunction "1_8") (pintype "passive"))
      (node (ref "X9") (pin "8") (pinfunction "1_8") (pintype "passive"))
    )
    (net (code "44") (name "LED_A1") (class "Default")
      (node (ref "IC5") (pin "37") (pinfunction "PE1_37") (pintype "bidirectional"))
      (node (ref "R2") (pin "1") (pinfunction "1_1") (pintype "passive"))
    )
    (net (code "45") (name "LED_A1_OUT") (class "Default")
      (node (ref "R5") (pin "2") (pinfunction "2_2") (pintype "passive"))
      (node (ref "X1") (pin "7") (pinfunction "1_7") (pintype "passive"))
      (node (ref "X2") (pin "7") (pinfunction "1_7") (pintype "passive"))
      (node (ref "X3") (pin "7") (pinfunction "1_7") (pintype "passive"))
      (node (ref "X4") (pin "7") (pinfunction "1_7") (pintype "passive"))
      (node (ref "X6") (pin "7") (pinfunction "1_7") (pintype "passive"))
      (node (ref "X7") (pin "7") (pinfunction "1_7") (pintype "passive"))
      (node (ref "X8") (pin "7") (pinfunction "1_7") (pintype "passive"))
      (node (ref "X9") (pin "7") (pinfunction "1_7") (pintype "passive"))
    )
    (net (code "46") (name "LED_A2") (class "Default")
      (node (ref "IC5") (pin "38") (pinfunction "PE2_38") (pintype "bidirectional"))
      (node (ref "R3") (pin "1") (pinfunction "1_1") (pintype "passive"))
    )
    (net (code "47") (name "LED_A2_OUT") (class "Default")
      (node (ref "R4") (pin "2") (pinfunction "2_2") (pintype "passive"))
      (node (ref "X1") (pin "6") (pinfunction "1_6") (pintype "passive"))
      (node (ref "X2") (pin "6") (pinfunction "1_6") (pintype "passive"))
      (node (ref "X3") (pin "6") (pinfunction "1_6") (pintype "passive"))
      (node (ref "X4") (pin "6") (pinfunction "1_6") (pintype "passive"))
      (node (ref "X6") (pin "6") (pinfunction "1_6") (pintype "passive"))
      (node (ref "X7") (pin "6") (pinfunction "1_6") (pintype "passive"))
      (node (ref "X8") (pin "6") (pinfunction "1_6") (pintype "passive"))
      (node (ref "X9") (pin "6") (pinfunction "1_6") (pintype "passive"))
    )
    (net (code "48") (name "LED_K0_OUT") (class "Default")
      (node (ref "IC3") (pin "18") (pinfunction "O1_18") (pintype "open_collector"))
      (node (ref "X3") (pin "5") (pinfunction "1_5") (pintype "passive"))
    )
    (net (code "49") (name "LED_K1_OUT") (class "Default")
      (node (ref "IC3") (pin "17") (pinfunction "O2_17") (pintype "open_collector"))
      (node (ref "X1") (pin "5") (pinfunction "1_5") (pintype "passive"))
    )
    (net (code "50") (name "LED_K2_OUT") (class "Default")
      (node (ref "IC3") (pin "16") (pinfunction "O3_16") (pintype "open_collector"))
      (node (ref "X2") (pin "5") (pinfunction "1_5") (pintype "passive"))
    )
    (net (code "51") (name "LED_K3_OUT") (class "Default")
      (node (ref "IC3") (pin "15") (pinfunction "O4_15") (pintype "open_collector"))
      (node (ref "X4") (pin "5") (pinfunction "1_5") (pintype "passive"))
    )
    (net (code "52") (name "LED_K4_OUT") (class "Default")
      (node (ref "IC3") (pin "14") (pinfunction "O5_14") (pintype "open_collector"))
      (node (ref "X8") (pin "5") (pinfunction "1_5") (pintype "passive"))
    )
    (net (code "53") (name "LED_K5_OUT") (class "Default")
      (node (ref "IC3") (pin "13") (pinfunction "O6_13") (pintype "open_collector"))
      (node (ref "X6") (pin "5") (pinfunction "1_5") (pintype "passive"))
    )
    (net (code "54") (name "LED_K6_OUT") (class "Default")
      (node (ref "IC3") (pin "12") (pinfunction "O7_12") (pintype "open_collector"))
      (node (ref "X7") (pin "5") (pinfunction "1_5") (pintype "passive"))
    )
    (net (code "55") (name "LED_K7_OUT") (class "Default")
      (node (ref "IC3") (pin "11") (pinfunction "O8_11") (pintype "open_collector"))
      (node (ref "X9") (pin "5") (pinfunction "1_5") (pintype "passive"))
    )
    (net (code "56") (name "MOTOR_A_IN1") (class "Default")
      (node (ref "IC5") (pin "41") (pinfunction "PE5_41") (pintype "bidirectional"))
      (node (ref "IC7") (pin "21") (pinfunction "AIN1_21") (pintype "bidirectional"))
    )
    (net (code "57") (name "MOTOR_A_IN2") (class "Default")
      (node (ref "IC5") (pin "40") (pinfunction "PE4_40") (pintype "bidirectional"))
      (node (ref "IC7") (pin "22") (pinfunction "AIN2_22") (pintype "bidirectional"))
    )
    (net (code "58") (name "MOTOR_A_OUT1") (class "Default")
      (node (ref "IC7") (pin "1") (pinfunction "A01_1") (pintype "bidirectional"))
      (node (ref "IC7") (pin "2") (pinfunction "A01_2") (pintype "bidirectional"))
      (node (ref "X12") (pin "4") (pinfunction "1_4") (pintype "passive"))
    )
    (net (code "59") (name "MOTOR_A_OUT2") (class "Default")
      (node (ref "IC7") (pin "5") (pinfunction "A02_5") (pintype "bidirectional"))
      (node (ref "IC7") (pin "6") (pinfunction "A02_6") (pintype "bidirectional"))
      (node (ref "X12") (pin "3") (pinfunction "1_3") (pintype "passive"))
    )
    (net (code "60") (name "MOTOR_A_PWM") (class "Default")
      (node (ref "IC5") (pin "19") (pinfunction "PC3_19") (pintype "bidirectional"))
      (node (ref "IC7") (pin "23") (pinfunction "PWMA_23") (pintype "bidirectional"))
    )
    (net (code "61") (name "MOTOR_B_IN1") (class "Default")
      (node (ref "IC5") (pin "42") (pinfunction "PE6_42") (pintype "bidirectional"))
      (node (ref "IC7") (pin "17") (pinfunction "BIN1_17") (pintype "bidirectional"))
    )
    (net (code "62") (name "MOTOR_B_IN2") (class "Default")
      (node (ref "IC5") (pin "43") (pinfunction "PE7_43") (pintype "bidirectional"))
      (node (ref "IC7") (pin "16") (pinfunction "BIN2_16") (pintype "bidirectional"))
    )
    (net (code "63") (name "MOTOR_B_OUT1") (class "Default")
      (node (ref "IC7") (pin "11") (pinfunction "B01_11") (pintype "bidirectional"))
      (node (ref "IC7") (pin "12") (pinfunction "B01_12") (pintype "bidirectional"))
      (node (ref "X12") (pin "1") (pinfunction "1_1") (pintype "passive"))
    )
    (net (code "64") (name "MOTOR_B_OUT2") (class "Default")
      (node (ref "IC7") (pin "7") (pinfunction "B02_7") (pintype "bidirectional"))
      (node (ref "IC7") (pin "8") (pinfunction "B02_8") (pintype "bidirectional"))
      (node (ref "X12") (pin "2") (pinfunction "1_2") (pintype "passive"))
    )
    (net (code "65") (name "MOTOR_B_PWM") (class "Default")
      (node (ref "IC5") (pin "18") (pinfunction "PC2_18") (pintype "bidirectional"))
      (node (ref "IC7") (pin "15") (pinfunction "PWMB_15") (pintype "bidirectional"))
    )
    (net (code "66") (name "MOTOR_STBY") (class "Default")
      (node (ref "IC5") (pin "4") (pinfunction "PA6_4") (pintype "bidirectional"))
      (node (ref "IC7") (pin "19") (pinfunction "STBY_19") (pintype "bidirectional"))
    )
    (net (code "67") (name "Net-(C11-Pad1)") (class "Default")
      (node (ref "C11") (pin "1") (pinfunction "1_1") (pintype "passive"))
      (node (ref "R18") (pin "2") (pinfunction "2_2") (pintype "passive"))
    )
    (net (code "68") (name "Net-(D1-PadLED_A)") (class "Default")
      (node (ref "D1") (pin "LED_A") (pinfunction "LED_A_LED_A") (pintype "bidirectional"))
      (node (ref "R25") (pin "1") (pinfunction "1_1") (pintype "passive"))
    )
    (net (code "69") (name "Net-(D2-PadLED_A)") (class "Default")
      (node (ref "D2") (pin "LED_A") (pinfunction "LED_A_LED_A") (pintype "bidirectional"))
      (node (ref "R26") (pin "1") (pinfunction "1_1") (pintype "passive"))
    )
    (net (code "70") (name "Net-(D3-PadLED_A)") (class "Default")
      (node (ref "D3") (pin "LED_A") (pinfunction "LED_A_LED_A") (pintype "bidirectional"))
      (node (ref "R31") (pin "1") (pinfunction "1_1") (pintype "passive"))
    )
    (net (code "71") (name "Net-(D4-PadLED_A)") (class "Default")
      (node (ref "D4") (pin "LED_A") (pinfunction "LED_A_LED_A") (pintype "bidirectional"))
      (node (ref "R32") (pin "1") (pinfunction "1_1") (pintype "passive"))
    )
    (net (code "72") (name "Net-(IC1-Y0)") (class "Default")
      (node (ref "IC1") (pin "15") (pinfunction "Y0_15") (pintype "output"))
      (node (ref "IC3") (pin "1") (pinfunction "I1_1") (pintype "input"))
    )
    (net (code "73") (name "Net-(IC1-Y1)") (class "Default")
      (node (ref "IC1") (pin "14") (pinfunction "Y1_14") (pintype "output"))
      (node (ref "IC3") (pin "2") (pinfunction "I2_2") (pintype "input"))
    )
    (net (code "74") (name "Net-(IC1-Y2)") (class "Default")
      (node (ref "IC1") (pin "13") (pinfunction "Y2_13") (pintype "output"))
      (node (ref "IC3") (pin "3") (pinfunction "I3_3") (pintype "input"))
    )
    (net (code "75") (name "Net-(IC1-Y3)") (class "Default")
      (node (ref "IC1") (pin "12") (pinfunction "Y3_12") (pintype "output"))
      (node (ref "IC3") (pin "4") (pinfunction "I4_4") (pintype "input"))
    )
    (net (code "76") (name "Net-(IC1-Y4)") (class "Default")
      (node (ref "IC1") (pin "11") (pinfunction "Y4_11") (pintype "output"))
      (node (ref "IC3") (pin "5") (pinfunction "I5_5") (pintype "input"))
    )
    (net (code "77") (name "Net-(IC1-Y5)") (class "Default")
      (node (ref "IC1") (pin "10") (pinfunction "Y5_10") (pintype "output"))
      (node (ref "IC3") (pin "6") (pinfunction "I6_6") (pintype "input"))
    )
    (net (code "78") (name "Net-(IC1-Y6)") (class "Default")
      (node (ref "IC1") (pin "9") (pinfunction "Y6_9") (pintype "output"))
      (node (ref "IC3") (pin "7") (pinfunction "I7_7") (pintype "input"))
    )
    (net (code "79") (name "Net-(IC1-Y7)") (class "Default")
      (node (ref "IC1") (pin "7") (pinfunction "Y7_7") (pintype "output"))
      (node (ref "IC3") (pin "8") (pinfunction "I8_8") (pintype "input"))
    )
    (net (code "80") (name "Net-(IC2-Y0)") (class "Default")
      (node (ref "IC2") (pin "15") (pinfunction "Y0_15") (pintype "output"))
      (node (ref "IC4") (pin "1") (pinfunction "I1_1") (pintype "input"))
    )
    (net (code "81") (name "Net-(IC2-Y1)") (class "Default")
      (node (ref "IC2") (pin "14") (pinfunction "Y1_14") (pintype "output"))
      (node (ref "IC4") (pin "2") (pinfunction "I2_2") (pintype "input"))
    )
    (net (code "82") (name "Net-(IC2-Y2)") (class "Default")
      (node (ref "IC2") (pin "13") (pinfunction "Y2_13") (pintype "output"))
      (node (ref "IC4") (pin "3") (pinfunction "I3_3") (pintype "input"))
    )
    (net (code "83") (name "Net-(IC2-Y3)") (class "Default")
      (node (ref "IC2") (pin "12") (pinfunction "Y3_12") (pintype "output"))
      (node (ref "IC4") (pin "4") (pinfunction "I4_4") (pintype "input"))
    )
    (net (code "84") (name "Net-(IC2-Y4)") (class "Default")
      (node (ref "IC2") (pin "11") (pinfunction "Y4_11") (pintype "output"))
      (node (ref "IC4") (pin "5") (pinfunction "I5_5") (pintype "input"))
    )
    (net (code "85") (name "Net-(IC2-Y5)") (class "Default")
      (node (ref "IC2") (pin "10") (pinfunction "Y5_10") (pintype "output"))
      (node (ref "IC4") (pin "6") (pinfunction "I6_6") (pintype "input"))
    )
    (net (code "86") (name "Net-(IC2-Y6)") (class "Default")
      (node (ref "IC2") (pin "9") (pinfunction "Y6_9") (pintype "output"))
      (node (ref "IC4") (pin "7") (pinfunction "I7_7") (pintype "input"))
    )
    (net (code "87") (name "Net-(IC2-Y7)") (class "Default")
      (node (ref "IC2") (pin "7") (pinfunction "Y7_7") (pintype "output"))
      (node (ref "IC4") (pin "8") (pinfunction "I8_8") (pintype "input"))
    )
    (net (code "88") (name "Net-(IC5-PA0)") (class "Default")
      (node (ref "IC5") (pin "62") (pinfunction "PA0_62") (pintype "bidirectional"))
      (node (ref "R8") (pin "2") (pinfunction "2_2") (pintype "passive"))
      (node (ref "R9") (pin "1") (pinfunction "1_1") (pintype "passive"))
    )
    (net (code "89") (name "Net-(IC5-PR0)") (class "Default")
      (node (ref "C7") (pin "2") (pinfunction "2_2") (pintype "passive"))
      (node (ref "IC5") (pin "58") (pinfunction "PR0_58") (pintype "bidirectional"))
      (node (ref "Q4") (pin "2") (pinfunction "2_2") (pintype "passive"))
    )
    (net (code "90") (name "Net-(IC5-PR1)") (class "Default")
      (node (ref "C8") (pin "2") (pinfunction "2_2") (pintype "passive"))
      (node (ref "IC5") (pin "59") (pinfunction "PR1_59") (pintype "bidirectional"))
      (node (ref "Q4") (pin "1") (pinfunction "1_1") (pintype "passive"))
    )
    (net (code "91") (name "Net-(IC8-FC2)") (class "Default")
      (node (ref "C12") (pin "1") (pinfunction "1_1") (pintype "passive"))
      (node (ref "IC8") (pin "2") (pinfunction "FC2_2") (pintype "bidirectional"))
    )
    (net (code "92") (name "Net-(IC8-VIN)") (class "Default")
      (node (ref "IC8") (pin "4") (pinfunction "VIN_4") (pintype "bidirectional"))
      (node (ref "R18") (pin "1") (pinfunction "1_1") (pintype "passive"))
      (node (ref "R19") (pin "2") (pinfunction "2_2") (pintype "passive"))
    )
    (net (code "93") (name "Net-(LED1-PadA)") (class "Default")
      (node (ref "LED1") (pin "A") (pinfunction "A_A") (pintype "passive"))
      (node (ref "R13") (pin "2") (pinfunction "2_2") (pintype "passive"))
    )
    (net (code "94") (name "Net-(LED2-PadA)") (class "Default")
      (node (ref "LED2") (pin "A") (pinfunction "A_A") (pintype "passive"))
      (node (ref "R14") (pin "2") (pinfunction "2_2") (pintype "passive"))
    )
    (net (code "95") (name "Net-(LED3-PadC)") (class "Default")
      (node (ref "LED3") (pin "C") (pinfunction "C_C") (pintype "passive"))
      (node (ref "R20") (pin "1") (pinfunction "1_1") (pintype "passive"))
    )
    (net (code "96") (name "Net-(Q1-PadG)") (class "Default")
      (node (ref "Q1") (pin "G") (pinfunction "G_G") (pintype "passive"))
      (node (ref "R1") (pin "2") (pinfunction "2_2") (pintype "passive"))
    )
    (net (code "97") (name "Net-(Q1-PadS)") (class "Default")
      (node (ref "Q1") (pin "S") (pinfunction "S_S") (pintype "passive"))
      (node (ref "R6") (pin "1") (pinfunction "1_1") (pintype "passive"))
    )
    (net (code "98") (name "Net-(Q2-PadG)") (class "Default")
      (node (ref "Q2") (pin "G") (pinfunction "G_G") (pintype "passive"))
      (node (ref "R2") (pin "2") (pinfunction "2_2") (pintype "passive"))
    )
    (net (code "99") (name "Net-(Q2-PadS)") (class "Default")
      (node (ref "Q2") (pin "S") (pinfunction "S_S") (pintype "passive"))
      (node (ref "R5") (pin "1") (pinfunction "1_1") (pintype "passive"))
    )
    (net (code "100") (name "Net-(Q3-PadG)") (class "Default")
      (node (ref "Q3") (pin "G") (pinfunction "G_G") (pintype "passive"))
      (node (ref "R3") (pin "2") (pinfunction "2_2") (pintype "passive"))
    )
    (net (code "101") (name "Net-(Q3-PadS)") (class "Default")
      (node (ref "Q3") (pin "S") (pinfunction "S_S") (pintype "passive"))
      (node (ref "R4") (pin "1") (pinfunction "1_1") (pintype "passive"))
    )
    (net (code "102") (name "Net-(Q5-PadG)") (class "Default")
      (node (ref "Q5") (pin "G") (pinfunction "G_G") (pintype "passive"))
      (node (ref "R11") (pin "2") (pinfunction "2_2") (pintype "passive"))
    )
    (net (code "103") (name "Net-(Q6-PadG)") (class "Default")
      (node (ref "Q6") (pin "G") (pinfunction "G_G") (pintype "passive"))
      (node (ref "R15") (pin "2") (pinfunction "2_2") (pintype "passive"))
    )
    (net (code "104") (name "Net-(Q7-G2)") (class "Default")
      (node (ref "Q7") (pin "4") (pinfunction "G2_4") (pintype "passive"))
      (node (ref "Q7") (pin "7") (pinfunction "D1_7") (pintype "bidirectional"))
      (node (ref "Q7") (pin "8") (pinfunction "D1_8") (pintype "bidirectional"))
      (node (ref "R23") (pin "2") (pinfunction "2_2") (pintype "passive"))
      (node (ref "R24") (pin "1") (pinfunction "1_1") (pintype "passive"))
    )
    (net (code "105") (name "Net-(S1-P)") (class "Default")
      (node (ref "C17") (pin "1") (pinfunction "1_1") (pintype "passive"))
      (node (ref "R24") (pin "2") (pinfunction "2_2") (pintype "passive"))
      (node (ref "S1") (pin "3") (pinfunction "P_3") (pintype "passive"))
      (node (ref "S1") (pin "4") (pinfunction "P1_4") (pintype "passive"))
    )
    (net (code "106") (name "Net-(X11J-1)") (class "Default")
      (node (ref "Q5") (pin "S") (pinfunction "S_S") (pintype "passive"))
      (node (ref "X11") (pin "9") (pinfunction "1_9") (pintype "passive"))
    )
    (net (code "107") (name "PDI_CLK") (class "Default")
      (node (ref "IC5") (pin "57") (pinfunction "~{RESET}/PDI_57") (pintype "bidirectional"))
      (node (ref "R7") (pin "2") (pinfunction "2_2") (pintype "passive"))
      (node (ref "X5") (pin "5") (pinfunction "1_5") (pintype "passive"))
    )
    (net (code "108") (name "PDI_DATA") (class "Default")
      (node (ref "IC5") (pin "56") (pinfunction "PDI_56") (pintype "bidirectional"))
      (node (ref "X5") (pin "1") (pinfunction "1_1") (pintype "passive"))
    )
    (net (code "109") (name "POWER_OFF") (class "Default")
      (node (ref "IC5") (pin "5") (pinfunction "PA7_5") (pintype "bidirectional"))
      (node (ref "Q7") (pin "2") (pinfunction "G1_2") (pintype "passive"))
      (node (ref "R30") (pin "2") (pinfunction "2_2") (pintype "passive"))
      (node (ref "S1") (pin "1") (pinfunction "S_1") (pintype "passive"))
      (node (ref "S1") (pin "2") (pinfunction "S1_2") (pintype "passive"))
    )
    (net (code "110") (name "RGB_LED_MK0") (class "Default")
      (node (ref "IC1") (pin "1") (pinfunction "A_1") (pintype "input"))
      (node (ref "IC5") (pin "51") (pinfunction "PF5_51") (pintype "bidirectional"))
    )
    (net (code "111") (name "RGB_LED_MK1") (class "Default")
      (node (ref "IC1") (pin "2") (pinfunction "B_2") (pintype "input"))
      (node (ref "IC5") (pin "50") (pinfunction "PF4_50") (pintype "bidirectional"))
    )
    (net (code "112") (name "RGB_LED_MK2") (class "Default")
      (node (ref "IC1") (pin "3") (pinfunction "C_3") (pintype "input"))
      (node (ref "IC5") (pin "49") (pinfunction "PF3_49") (pintype "bidirectional"))
    )
    (net (code "113") (name "RPI_RX") (class "Default")
      (node (ref "IC5") (pin "29") (pinfunction "PD3_29") (pintype "bidirectional"))
      (node (ref "IC9") (pin "GPIO_15") (pinfunction "GPIO_15_GPIO_15") (pintype "bidirectional"))
    )
    (net (code "114") (name "RPI_TX") (class "Default")
      (node (ref "IC5") (pin "28") (pinfunction "PD2_28") (pintype "bidirectional"))
      (node (ref "IC9") (pin "GPIO_14") (pinfunction "GPIO_14_GPIO_14") (pintype "bidirectional"))
    )
    (net (code "115") (name "SCL") (class "Default")
      (node (ref "IC5") (pin "17") (pinfunction "PC1_17") (pintype "bidirectional"))
      (node (ref "IC6") (pin "SCL") (pinfunction "SCL_SCL") (pintype "bidirectional"))
      (node (ref "IC9") (pin "GPIO_1") (pinfunction "GPIO_1_GPIO_1") (pintype "bidirectional"))
      (node (ref "R12") (pin "2") (pinfunction "2_2") (pintype "passive"))
      (node (ref "X10") (pin "3") (pinfunction "1_3") (pintype "passive"))
    )
    (net (code "116") (name "SDA") (class "Default")
      (node (ref "IC5") (pin "16") (pinfunction "PC0_16") (pintype "bidirectional"))
      (node (ref "IC6") (pin "SDA") (pinfunction "SDA_SDA") (pintype "bidirectional"))
      (node (ref "IC9") (pin "GPIO_0") (pinfunction "GPIO_0_GPIO_0") (pintype "bidirectional"))
      (node (ref "R10") (pin "2") (pinfunction "2_2") (pintype "passive"))
      (node (ref "X10") (pin "4") (pinfunction "1_4") (pintype "passive"))
    )
    (net (code "117") (name "SPEAKER_O1") (class "Default")
      (node (ref "IC8") (pin "8") (pinfunction "VO2_8") (pintype "bidirectional"))
      (node (ref "X13") (pin "2") (pinfunction "1_2") (pintype "passive"))
    )
    (net (code "118") (name "SPEAKER_O2") (class "Default")
      (node (ref "IC8") (pin "5") (pinfunction "VO1_5") (pintype "bidirectional"))
      (node (ref "R19") (pin "1") (pinfunction "1_1") (pintype "passive"))
      (node (ref "X13") (pin "3") (pinfunction "1_3") (pintype "passive"))
    )
    (net (code "119") (name "unconnected-(IC3-CD+-Pad10)") (class "Default")
      (node (ref "IC3") (pin "10") (pinfunction "CD+_10") (pintype "passive"))
    )
    (net (code "120") (name "unconnected-(IC4-CD+-Pad10)") (class "Default")
      (node (ref "IC4") (pin "10") (pinfunction "CD+_10") (pintype "passive"))
    )
    (net (code "121") (name "unconnected-(IC5-PA5-Pad3)") (class "Default")
      (node (ref "IC5") (pin "3") (pinfunction "PA5_3") (pintype "bidirectional"))
    )
    (net (code "122") (name "unconnected-(IC5-PF7-Pad55)") (class "Default")
      (node (ref "IC5") (pin "55") (pinfunction "PF7_55") (pintype "bidirectional"))
    )
    (net (code "123") (name "unconnected-(IC6-PadA_INT1)") (class "Default")
      (node (ref "IC6") (pin "A_INT1") (pinfunction "A_INT1_A_INT1") (pintype "bidirectional"))
    )
    (net (code "124") (name "unconnected-(IC6-PadG_INT)") (class "Default")
      (node (ref "IC6") (pin "G_INT") (pinfunction "G_INT_G_INT") (pintype "bidirectional"))
    )
    (net (code "125") (name "unconnected-(IC6-PadM_DRDY)") (class "Default")
      (node (ref "IC6") (pin "M_DRDY") (pinfunction "M_DRDY_M_DRDY") (pintype "bidirectional"))
    )
    (net (code "126") (name "unconnected-(IC6-PadP_E0C)") (class "Default")
      (node (ref "IC6") (pin "P_E0C") (pinfunction "P_E0C_P_E0C") (pintype "bidirectional"))
    )
    (net (code "127") (name "unconnected-(IC6-PadP_XCLR)") (class "Default")
      (node (ref "IC6") (pin "P_XCLR") (pinfunction "P_XCLR_P_XCLR") (pintype "bidirectional"))
    )
    (net (code "128") (name "unconnected-(IC8-FC1-Pad3)") (class "Default")
      (node (ref "IC8") (pin "3") (pinfunction "FC1_3") (pintype "bidirectional"))
    )
    (net (code "129") (name "unconnected-(IC9-PadGPIO_4)") (class "Default")
      (node (ref "IC9") (pin "GPIO_4") (pinfunction "GPIO_4_GPIO_4") (pintype "bidirectional"))
    )
    (net (code "130") (name "unconnected-(IC9-PadGPIO_7)") (class "Default")
      (node (ref "IC9") (pin "GPIO_7") (pinfunction "GPIO_7_GPIO_7") (pintype "bidirectional"))
    )
    (net (code "131") (name "unconnected-(IC9-PadGPIO_8)") (class "Default")
      (node (ref "IC9") (pin "GPIO_8") (pinfunction "GPIO_8_GPIO_8") (pintype "bidirectional"))
    )
    (net (code "132") (name "unconnected-(IC9-PadGPIO_9)") (class "Default")
      (node (ref "IC9") (pin "GPIO_9") (pinfunction "GPIO_9_GPIO_9") (pintype "bidirectional"))
    )
    (net (code "133") (name "unconnected-(IC9-PadGPIO_10)") (class "Default")
      (node (ref "IC9") (pin "GPIO_10") (pinfunction "GPIO_10_GPIO_10") (pintype "bidirectional"))
    )
    (net (code "134") (name "unconnected-(IC9-PadGPIO_11)") (class "Default")
      (node (ref "IC9") (pin "GPIO_11") (pinfunction "GPIO_11_GPIO_11") (pintype "bidirectional"))
    )
    (net (code "135") (name "unconnected-(IC9-PadGPIO_17)") (class "Default")
      (node (ref "IC9") (pin "GPIO_17") (pinfunction "GPIO_17_GPIO_17") (pintype "bidirectional"))
    )
    (net (code "136") (name "unconnected-(IC9-PadGPIO_18)") (class "Default")
      (node (ref "IC9") (pin "GPIO_18") (pinfunction "GPIO_18_GPIO_18") (pintype "bidirectional"))
    )
    (net (code "137") (name "unconnected-(IC9-PadGPIO_21)") (class "Default")
      (node (ref "IC9") (pin "GPIO_21") (pinfunction "GPIO_21_GPIO_21") (pintype "bidirectional"))
    )
    (net (code "138") (name "unconnected-(IC9-PadGPIO_22)") (class "Default")
      (node (ref "IC9") (pin "GPIO_22") (pinfunction "GPIO_22_GPIO_22") (pintype "bidirectional"))
    )
    (net (code "139") (name "unconnected-(IC9-PadGPIO_23)") (class "Default")
      (node (ref "IC9") (pin "GPIO_23") (pinfunction "GPIO_23_GPIO_23") (pintype "bidirectional"))
    )
    (net (code "140") (name "unconnected-(IC9-PadGPIO_24)") (class "Default")
      (node (ref "IC9") (pin "GPIO_24") (pinfunction "GPIO_24_GPIO_24") (pintype "bidirectional"))
    )
    (net (code "141") (name "unconnected-(IC9-PadGPIO_25)") (class "Default")
      (node (ref "IC9") (pin "GPIO_25") (pinfunction "GPIO_25_GPIO_25") (pintype "bidirectional"))
    )
    (net (code "142") (name "unconnected-(X5C-1-Pad3)") (class "Default")
      (node (ref "X5") (pin "3") (pinfunction "1_3") (pintype "passive"))
    )
    (net (code "143") (name "unconnected-(X5D-1-Pad4)") (class "Default")
      (node (ref "X5") (pin "4") (pinfunction "1_4") (pintype "passive"))
    )
    (net (code "144") (name "unconnected-(X10F-1-Pad6)") (class "Default")
      (node (ref "X10") (pin "6") (pinfunction "1_6") (pintype "passive"))
    )
    (net (code "145") (name "unconnected-(X11-Pad1)") (class "Default")
      (node (ref "X11") (pin "1") (pinfunction "1_1") (pintype "passive"))
    )
  )
)
